# p7ii-001.net
KiCad netlist of a schematic drawn in EAGLE
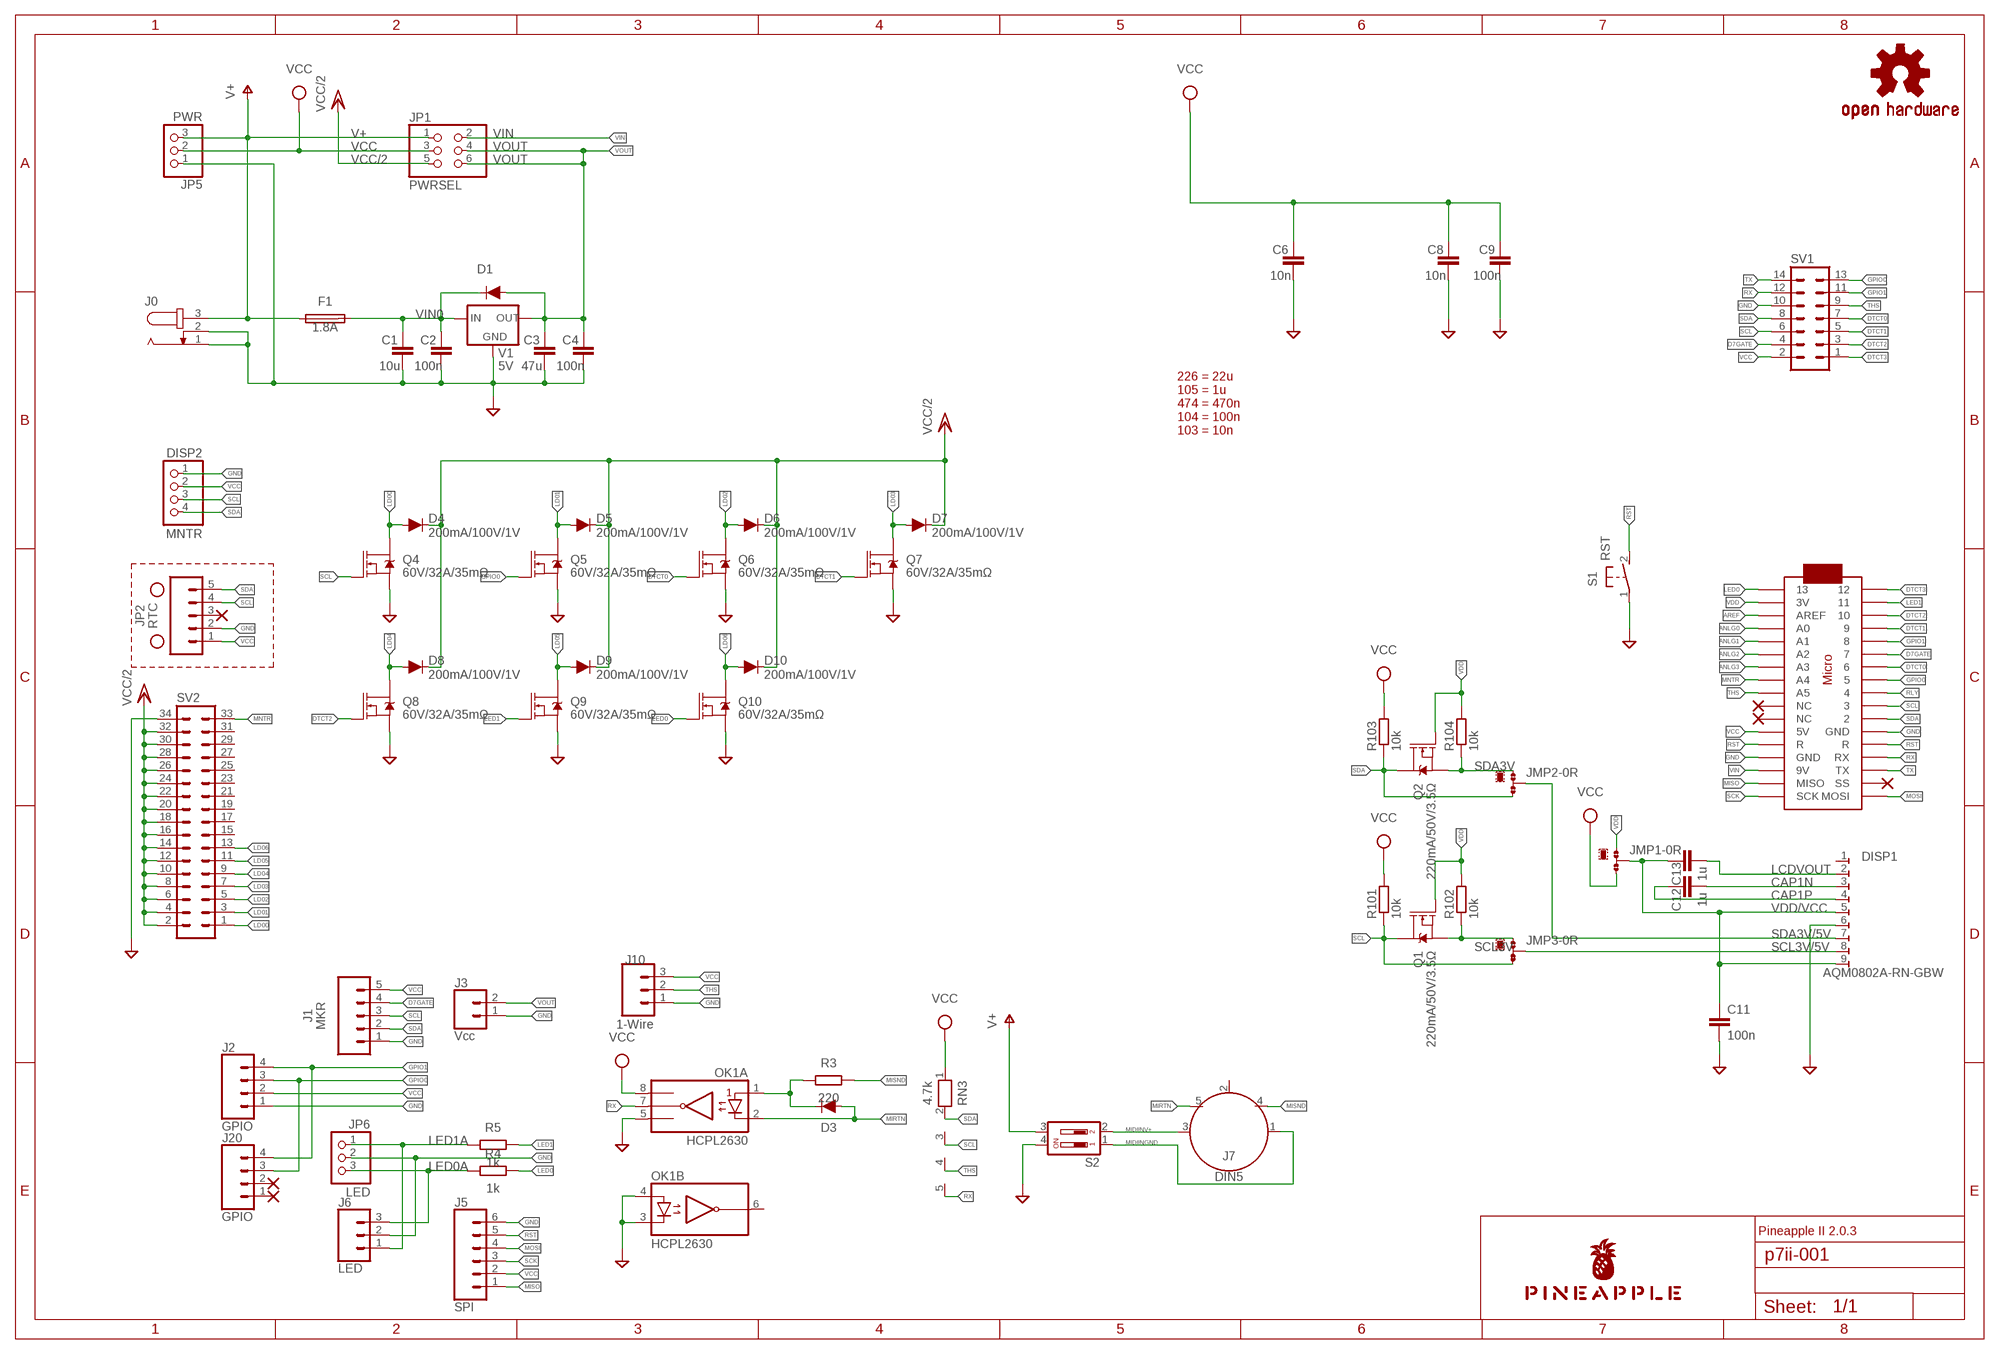
[diagram p0: schematic, sheet 1]

(export (version "E")
  (design (tool "Eeschema 10.0.6"))
  (components
    (comp (ref "C1")
      (value "10u")
      (footprint "eagle-import:C025-030X050")
      (libsource (lib "eagle-import") (part "C-EU025-030X050"))
    )
    (comp (ref "C2")
      (value "100n")
      (footprint "eagle-import:C025-024X044")
      (libsource (lib "eagle-import") (part "C-EU025-024X044"))
    )
    (comp (ref "C3")
      (value "47u")
      (footprint "eagle-import:C025-050X050")
      (libsource (lib "eagle-import") (part "C-EU025-050X050"))
    )
    (comp (ref "C4")
      (value "100n")
      (footprint "eagle-import:C025-024X044")
      (libsource (lib "eagle-import") (part "C-EU025-024X044"))
    )
    (comp (ref "C6")
      (value "10n")
      (footprint "eagle-import:C025-024X044")
      (libsource (lib "eagle-import") (part "resistor_348_C-EU025-024X044"))
    )
    (comp (ref "C8")
      (value "10n")
      (footprint "eagle-import:C025-024X044")
      (libsource (lib "eagle-import") (part "resistor_348_C-EU025-024X044"))
    )
    (comp (ref "C9")
      (value "100n")
      (footprint "eagle-import:C025-024X044")
      (libsource (lib "eagle-import") (part "resistor_348_C-EU025-024X044"))
    )
    (comp (ref "C11")
      (value "100n")
      (footprint "eagle-import:C025-024X044")
      (libsource (lib "eagle-import") (part "C-EU025-024X044"))
    )
    (comp (ref "C12")
      (value "1u")
      (footprint "eagle-import:C050-024X044")
      (libsource (lib "eagle-import") (part "C-EU050-024X044"))
    )
    (comp (ref "C13")
      (value "1u")
      (footprint "eagle-import:C050-024X044")
      (libsource (lib "eagle-import") (part "C-EU050-024X044"))
    )
    (comp (ref "D1")
      (value "DIODE-1N4148")
      (footprint "eagle-import:DIODE-1N4148")
      (libsource (lib "eagle-import") (part "DIODE-1N4148"))
    )
    (comp (ref "D3")
      (value "DIODE-1N4148")
      (footprint "eagle-import:DIODE-1N4148")
      (libsource (lib "eagle-import") (part "DIODE-1N4148"))
    )
    (comp (ref "D4")
      (value "200mA/100V/1V")
      (footprint "eagle-import:DIODE-1N4148")
      (libsource (lib "eagle-import") (part "DIODE-1N4148"))
    )
    (comp (ref "D5")
      (value "200mA/100V/1V")
      (footprint "eagle-import:DIODE-1N4148")
      (libsource (lib "eagle-import") (part "DIODE-1N4148"))
    )
    (comp (ref "D6")
      (value "200mA/100V/1V")
      (footprint "eagle-import:DIODE-1N4148")
      (libsource (lib "eagle-import") (part "DIODE-1N4148"))
    )
    (comp (ref "D7")
      (value "200mA/100V/1V")
      (footprint "eagle-import:DIODE-1N4148")
      (libsource (lib "eagle-import") (part "DIODE-1N4148"))
    )
    (comp (ref "D8")
      (value "200mA/100V/1V")
      (footprint "eagle-import:DIODE-1N4148")
      (libsource (lib "eagle-import") (part "DIODE-1N4148"))
    )
    (comp (ref "D9")
      (value "200mA/100V/1V")
      (footprint "eagle-import:DIODE-1N4148")
      (libsource (lib "eagle-import") (part "DIODE-1N4148"))
    )
    (comp (ref "D10")
      (value "200mA/100V/1V")
      (footprint "eagle-import:DIODE-1N4148")
      (libsource (lib "eagle-import") (part "DIODE-1N4148"))
    )
    (comp (ref "DISP1")
      (value "AQM0802A-RN-GBW")
      (footprint "eagle-import:AQM0802A-RN-GBW-FOOTPRINT")
      (libsource (lib "eagle-import") (part "AQM0802A-RN-GBW"))
    )
    (comp (ref "DISP2")
      (value "MNTR")
      (footprint "eagle-import:1X04")
      (libsource (lib "eagle-import") (part "PINHD-1X4"))
    )
    (comp (ref "F1")
      (value "1.8A")
      (footprint "eagle-import:TE5")
      (libsource (lib "eagle-import") (part "TE5"))
    )
    (comp (ref "H1")
      (value "STAND-OFF")
      (footprint "eagle-import:STAND-OFF")
      (libsource (lib "eagle-import") (part "STAND-OFF"))
    )
    (comp (ref "H2")
      (value "STAND-OFF")
      (footprint "eagle-import:STAND-OFF")
      (libsource (lib "eagle-import") (part "STAND-OFF"))
    )
    (comp (ref "J0")
      (value "JACK-PLUG0")
      (footprint "eagle-import:SPC4077")
      (libsource (lib "eagle-import") (part "JACK-PLUG0"))
    )
    (comp (ref "J1")
      (value "MKR")
      (footprint "eagle-import:JST-5-PTH")
      (libsource (lib "eagle-import") (part "CONN_05JST"))
    )
    (comp (ref "J2")
      (value "GPIO")
      (footprint "eagle-import:JST-4-PTH")
      (libsource (lib "eagle-import") (part "CONN_04JST-PTH"))
    )
    (comp (ref "J3")
      (value "Vcc")
      (footprint "eagle-import:JST-2-PTH")
      (libsource (lib "eagle-import") (part "CONN_02JST-PTH-2"))
    )
    (comp (ref "J5")
      (value "SPI")
      (footprint "eagle-import:1X06_1.27MM")
      (libsource (lib "eagle-import") (part "CONN_061.27MM"))
    )
    (comp (ref "J6")
      (value "LED")
      (footprint "eagle-import:JST-3-PTH-VERT")
      (libsource (lib "eagle-import") (part "CONN_03JST-PTH-VERT"))
    )
    (comp (ref "J7")
      (value "DIN5")
      (footprint "eagle-import:DIN5-RA-PTH")
      (libsource (lib "eagle-import") (part "DIN5"))
    )
    (comp (ref "J10")
      (value "1-Wire")
      (footprint "eagle-import:JST-3-PTH-VERT")
      (libsource (lib "eagle-import") (part "CONN_03JST-PTH-VERT"))
    )
    (comp (ref "J20")
      (value "GPIO")
      (footprint "eagle-import:1X04_1.27MM")
      (libsource (lib "eagle-import") (part "CONN_041.27MM"))
    )
    (comp (ref "JMP1")
      (value "0R-JUMPA")
      (footprint "eagle-import:A0R-JMP")
      (libsource (lib "eagle-import") (part "0R-JUMPA"))
    )
    (comp (ref "JMP2")
      (value "0R-JUMPA")
      (footprint "eagle-import:A0R-JMP")
      (libsource (lib "eagle-import") (part "0R-JUMPA"))
    )
    (comp (ref "JMP3")
      (value "0R-JUMPA")
      (footprint "eagle-import:A0R-JMP")
      (libsource (lib "eagle-import") (part "0R-JUMPA"))
    )
    (comp (ref "JP1")
      (value "PWRSEL")
      (footprint "eagle-import:2X03")
      (libsource (lib "eagle-import") (part "PINHD-2X3"))
    )
    (comp (ref "JP2")
      (value "RTC")
      (footprint "eagle-import:1X05")
      (libsource (lib "eagle-import") (part "CONN_05"))
    )
    (comp (ref "JP5")
      (value "PWR")
      (footprint "eagle-import:1X03")
      (libsource (lib "eagle-import") (part "PINHD-1X3"))
    )
    (comp (ref "JP6")
      (value "LED")
      (footprint "eagle-import:1X03")
      (libsource (lib "eagle-import") (part "PINHD-1X3"))
    )
    (comp (ref "LOGO1")
      (value "OSHW-LOGOS-COPPER")
      (footprint "eagle-import:OSHW-LOGO-S_COPPER")
      (libsource (lib "eagle-import") (part "OSHW-LOGOS-COPPER"))
    )
    (comp (ref "MC1")
      (value "ARDUINOMICRO")
      (footprint "eagle-import:ARDUINOMICRO")
      (libsource (lib "eagle-import") (part "ARDUINOMICRO"))
    )
    (comp (ref "OK1")
      (value "HCPL2630")
      (footprint "eagle-import:DIL08")
      (fields (field (name "MF") "AGILENT TECHNOLOGIES") (field (name "MPN") "HCPL-2630-000E"))
      (libsource (lib "eagle-import") (part "HCPL2630"))
    )
    (comp (ref "Q1")
      (value "220mA/50V/3.5Ω")
      (footprint "eagle-import:SOT23-3")
      (libsource (lib "eagle-import") (part "MOSFET-NCH-BSS138"))
    )
    (comp (ref "Q2")
      (value "220mA/50V/3.5Ω")
      (footprint "eagle-import:SOT23-3")
      (libsource (lib "eagle-import") (part "MOSFET-NCH-BSS138"))
    )
    (comp (ref "Q4")
      (value "60V/32A/35mΩ")
      (footprint "eagle-import:TO220V")
      (libsource (lib "eagle-import") (part "MOSFET-NCH-FQP30N06L"))
    )
    (comp (ref "Q5")
      (value "60V/32A/35mΩ")
      (footprint "eagle-import:TO220V")
      (libsource (lib "eagle-import") (part "MOSFET-NCH-FQP30N06L"))
    )
    (comp (ref "Q6")
      (value "60V/32A/35mΩ")
      (footprint "eagle-import:TO220V")
      (libsource (lib "eagle-import") (part "MOSFET-NCH-FQP30N06L"))
    )
    (comp (ref "Q7")
      (value "60V/32A/35mΩ")
      (footprint "eagle-import:TO220V")
      (libsource (lib "eagle-import") (part "MOSFET-NCH-FQP30N06L"))
    )
    (comp (ref "Q8")
      (value "60V/32A/35mΩ")
      (footprint "eagle-import:TO220V")
      (libsource (lib "eagle-import") (part "MOSFET-NCH-FQP30N06L"))
    )
    (comp (ref "Q9")
      (value "60V/32A/35mΩ")
      (footprint "eagle-import:TO220V")
      (libsource (lib "eagle-import") (part "MOSFET-NCH-FQP30N06L"))
    )
    (comp (ref "Q10")
      (value "60V/32A/35mΩ")
      (footprint "eagle-import:TO220V")
      (libsource (lib "eagle-import") (part "MOSFET-NCH-FQP30N06L"))
    )
    (comp (ref "R3")
      (value "220")
      (footprint "eagle-import:0204_5")
      (libsource (lib "eagle-import") (part "resistor_348_R-EU_0204/5"))
    )
    (comp (ref "R4")
      (value "1k")
      (footprint "eagle-import:0204_5")
      (libsource (lib "eagle-import") (part "resistor_348_R-EU_0204/5"))
    )
    (comp (ref "R5")
      (value "1k")
      (footprint "eagle-import:0204_5")
      (libsource (lib "eagle-import") (part "resistor_348_R-EU_0204/5"))
    )
    (comp (ref "R101")
      (value "10k")
      (footprint "eagle-import:M2012")
      (libsource (lib "eagle-import") (part "R-EU_M2012"))
    )
    (comp (ref "R102")
      (value "10k")
      (footprint "eagle-import:M2012")
      (libsource (lib "eagle-import") (part "R-EU_M2012"))
    )
    (comp (ref "R103")
      (value "10k")
      (footprint "eagle-import:M2012")
      (libsource (lib "eagle-import") (part "R-EU_M2012"))
    )
    (comp (ref "R104")
      (value "10k")
      (footprint "eagle-import:M2012")
      (libsource (lib "eagle-import") (part "R-EU_M2012"))
    )
    (comp (ref "RN3")
      (value "4.7k")
      (footprint "eagle-import:RN-5")
      (libsource (lib "eagle-import") (part "RN04"))
    )
    (comp (ref "S1")
      (value "RST")
      (footprint "eagle-import:B3F-31XX")
      (fields (field (name "MPN") "B3F-3100"))
      (libsource (lib "eagle-import") (part "31-XX"))
    )
    (comp (ref "S2")
      (value "DIP02YL")
      (footprint "eagle-import:DIP02YL")
      (libsource (lib "eagle-import") (part "DIP02YL"))
    )
    (comp (ref "SV1")
      (value "ML14")
      (footprint "eagle-import:ML14")
      (libsource (lib "eagle-import") (part "ML14"))
    )
    (comp (ref "SV2")
      (value "ML34L")
      (footprint "eagle-import:ML34L")
      (libsource (lib "eagle-import") (part "ML34L"))
    )
    (comp (ref "U$1")
      (value "PINEAPPLE450_SILK")
      (footprint "eagle-import:PINEAPPLE450_SILK")
      (libsource (lib "eagle-import") (part "PINEAPPLE450_SILK"))
    )
    (comp (ref "V1")
      (value "5V")
      (footprint "eagle-import:78XXS")
      (libsource (lib "eagle-import") (part "78XXS"))
    )
  )
  (nets
    (net (code "1") (name "/CAP1N") (class "Default")
      (node (ref "C12") (pin "2") (pinfunction "2_2") (pintype "passive"))
      (node (ref "DISP1") (pin "3") (pinfunction "3_3") (pintype "passive"))
    )
    (net (code "2") (name "/CAP1P") (class "Default")
      (node (ref "C12") (pin "1") (pinfunction "1_1") (pintype "passive"))
      (node (ref "DISP1") (pin "4") (pinfunction "4_4") (pintype "passive"))
    )
    (net (code "3") (name "/LCDVOUT") (class "Default")
      (node (ref "C13") (pin "2") (pinfunction "2_2") (pintype "passive"))
      (node (ref "DISP1") (pin "2") (pinfunction "2_2") (pintype "passive"))
    )
    (net (code "4") (name "/LED0A") (class "Default")
      (node (ref "J6") (pin "3") (pinfunction "3_3") (pintype "passive"))
      (node (ref "JP6") (pin "3") (pinfunction "3_3") (pintype "passive"))
      (node (ref "R4") (pin "1") (pinfunction "1_1") (pintype "passive"))
    )
    (net (code "5") (name "/LED1A") (class "Default")
      (node (ref "J6") (pin "1") (pinfunction "1_1") (pintype "passive"))
      (node (ref "JP6") (pin "1") (pinfunction "1_1") (pintype "passive"))
      (node (ref "R5") (pin "1") (pinfunction "1_1") (pintype "passive"))
    )
    (net (code "6") (name "/MIDIINGND") (class "Default")
      (node (ref "J7") (pin "1") (pinfunction "1_1") (pintype "bidirectional"))
      (node (ref "S2") (pin "1") (pinfunction "1_1") (pintype "passive"))
    )
    (net (code "7") (name "/MIDIINV+") (class "Default")
      (node (ref "J7") (pin "3") (pinfunction "3_3") (pintype "bidirectional"))
      (node (ref "S2") (pin "2") (pinfunction "2_2") (pintype "passive"))
    )
    (net (code "8") (name "/SCL3V") (class "Default")
      (node (ref "JMP3") (pin "1") (pinfunction "1_1") (pintype "passive"))
      (node (ref "Q1") (pin "2") (pinfunction "S_2") (pintype "bidirectional"))
      (node (ref "R102") (pin "1") (pinfunction "1_1") (pintype "passive"))
    )
    (net (code "9") (name "/SCL3V{slash}5V") (class "Default")
      (node (ref "DISP1") (pin "8") (pinfunction "8_8") (pintype "passive"))
      (node (ref "JMP3") (pin "2") (pinfunction "2_2") (pintype "passive"))
    )
    (net (code "10") (name "/SDA3V") (class "Default")
      (node (ref "JMP2") (pin "1") (pinfunction "1_1") (pintype "passive"))
      (node (ref "Q2") (pin "2") (pinfunction "S_2") (pintype "bidirectional"))
      (node (ref "R104") (pin "1") (pinfunction "1_1") (pintype "passive"))
    )
    (net (code "11") (name "/SDA3V{slash}5V") (class "Default")
      (node (ref "DISP1") (pin "7") (pinfunction "7_7") (pintype "passive"))
      (node (ref "JMP2") (pin "2") (pinfunction "2_2") (pintype "passive"))
    )
    (net (code "12") (name "/VDD{slash}VCC") (class "Default")
      (node (ref "C11") (pin "1") (pinfunction "1_1") (pintype "passive"))
      (node (ref "C13") (pin "1") (pinfunction "1_1") (pintype "passive"))
      (node (ref "DISP1") (pin "5") (pinfunction "5_5") (pintype "passive"))
      (node (ref "DISP1") (pin "9") (pinfunction "9_9") (pintype "passive"))
      (node (ref "JMP1") (pin "2") (pinfunction "2_2") (pintype "passive"))
    )
    (net (code "13") (name "/VIN0") (class "Default")
      (node (ref "C1") (pin "1") (pinfunction "1_1") (pintype "passive"))
      (node (ref "C2") (pin "1") (pinfunction "1_1") (pintype "passive"))
      (node (ref "D1") (pin "C") (pinfunction "C_C") (pintype "passive"))
      (node (ref "F1") (pin "2") (pinfunction "2_2") (pintype "passive"))
      (node (ref "V1") (pin "IN") (pinfunction "IN_IN") (pintype "input"))
    )
    (net (code "14") (name "ANLG0") (class "Default")
      (node (ref "MC1") (pin "P$31") (pinfunction "A0_P$31") (pintype "bidirectional"))
    )
    (net (code "15") (name "ANLG1") (class "Default")
      (node (ref "MC1") (pin "P$30") (pinfunction "A1_P$30") (pintype "bidirectional"))
    )
    (net (code "16") (name "ANLG2") (class "Default")
      (node (ref "MC1") (pin "P$29") (pinfunction "A2_P$29") (pintype "bidirectional"))
    )
    (net (code "17") (name "ANLG3") (class "Default")
      (node (ref "MC1") (pin "P$28") (pinfunction "A3_P$28") (pintype "bidirectional"))
    )
    (net (code "18") (name "AREF") (class "Default")
      (node (ref "MC1") (pin "P$32") (pinfunction "AREF_P$32") (pintype "bidirectional"))
    )
    (net (code "19") (name "D7GATE") (class "Default")
      (node (ref "J1") (pin "4") (pinfunction "4_4") (pintype "passive"))
      (node (ref "MC1") (pin "P$6") (pinfunction "7_P$6") (pintype "bidirectional"))
      (node (ref "SV1") (pin "4") (pinfunction "4_4") (pintype "passive"))
    )
    (net (code "20") (name "DTCT0") (class "Default")
      (node (ref "MC1") (pin "P$7") (pinfunction "6_P$7") (pintype "bidirectional"))
      (node (ref "Q6") (pin "1") (pinfunction "G_1") (pintype "bidirectional"))
      (node (ref "SV1") (pin "7") (pinfunction "7_7") (pintype "passive"))
    )
    (net (code "21") (name "DTCT1") (class "Default")
      (node (ref "MC1") (pin "P$4") (pinfunction "9_P$4") (pintype "bidirectional"))
      (node (ref "Q7") (pin "1") (pinfunction "G_1") (pintype "bidirectional"))
      (node (ref "SV1") (pin "5") (pinfunction "5_5") (pintype "passive"))
    )
    (net (code "22") (name "DTCT2") (class "Default")
      (node (ref "MC1") (pin "P$3") (pinfunction "10_P$3") (pintype "bidirectional"))
      (node (ref "Q8") (pin "1") (pinfunction "G_1") (pintype "bidirectional"))
      (node (ref "SV1") (pin "3") (pinfunction "3_3") (pintype "passive"))
    )
    (net (code "23") (name "DTCT3") (class "Default")
      (node (ref "MC1") (pin "P$1") (pinfunction "12_P$1") (pintype "bidirectional"))
      (node (ref "SV1") (pin "1") (pinfunction "1_1") (pintype "passive"))
    )
    (net (code "24") (name "GND") (class "Default")
      (node (ref "C1") (pin "2") (pinfunction "2_2") (pintype "passive"))
      (node (ref "C11") (pin "2") (pinfunction "2_2") (pintype "passive"))
      (node (ref "C2") (pin "2") (pinfunction "2_2") (pintype "passive"))
      (node (ref "C3") (pin "2") (pinfunction "2_2") (pintype "passive"))
      (node (ref "C4") (pin "2") (pinfunction "2_2") (pintype "passive"))
      (node (ref "C6") (pin "2") (pinfunction "2_2") (pintype "passive"))
      (node (ref "C8") (pin "2") (pinfunction "2_2") (pintype "passive"))
      (node (ref "C9") (pin "2") (pinfunction "2_2") (pintype "passive"))
      (node (ref "DISP1") (pin "6") (pinfunction "6_6") (pintype "passive"))
      (node (ref "DISP2") (pin "1") (pinfunction "1_1") (pintype "passive"))
      (node (ref "J0") (pin "1") (pinfunction "1_1") (pintype "passive"))
      (node (ref "J0") (pin "2") (pinfunction "2_2") (pintype "passive"))
      (node (ref "J1") (pin "1") (pinfunction "1_1") (pintype "passive"))
      (node (ref "J10") (pin "1") (pinfunction "1_1") (pintype "passive"))
      (node (ref "J2") (pin "1") (pinfunction "1_1") (pintype "passive"))
      (node (ref "J3") (pin "1") (pinfunction "1_1") (pintype "passive"))
      (node (ref "J5") (pin "6") (pinfunction "6_6") (pintype "passive"))
      (node (ref "J6") (pin "2") (pinfunction "2_2") (pintype "passive"))
      (node (ref "JP2") (pin "2") (pinfunction "2_2") (pintype "passive"))
      (node (ref "JP5") (pin "1") (pinfunction "1_1") (pintype "passive"))
      (node (ref "JP6") (pin "2") (pinfunction "2_2") (pintype "passive"))
      (node (ref "MC1") (pin "P$12") (pinfunction "GND_P$12") (pintype "bidirectional"))
      (node (ref "MC1") (pin "P$21") (pinfunction "GND_P$21") (pintype "bidirectional"))
      (node (ref "OK1") (pin "3") (pinfunction "C2_3") (pintype "passive"))
      (node (ref "OK1") (pin "4") (pinfunction "A2_4") (pintype "passive"))
      (node (ref "OK1") (pin "5") (pinfunction "GND_5") (pintype "passive"))
      (node (ref "Q10") (pin "3") (pinfunction "S_3") (pintype "bidirectional"))
      (node (ref "Q4") (pin "3") (pinfunction "S_3") (pintype "bidirectional"))
      (node (ref "Q5") (pin "3") (pinfunction "S_3") (pintype "bidirectional"))
      (node (ref "Q6") (pin "3") (pinfunction "S_3") (pintype "bidirectional"))
      (node (ref "Q7") (pin "3") (pinfunction "S_3") (pintype "bidirectional"))
      (node (ref "Q8") (pin "3") (pinfunction "S_3") (pintype "bidirectional"))
      (node (ref "Q9") (pin "3") (pinfunction "S_3") (pintype "bidirectional"))
      (node (ref "S1") (pin "1") (pinfunction "P_1") (pintype "passive"))
      (node (ref "S2") (pin "4") (pinfunction "4_4") (pintype "passive"))
      (node (ref "SV1") (pin "10") (pinfunction "10_10") (pintype "passive"))
      (node (ref "SV2") (pin "34") (pinfunction "34_34") (pintype "passive"))
      (node (ref "V1") (pin "GND") (pinfunction "GND_GND") (pintype "input"))
    )
    (net (code "25") (name "GPIO0") (class "Default")
      (node (ref "J2") (pin "3") (pinfunction "3_3") (pintype "passive"))
      (node (ref "J20") (pin "3") (pinfunction "3_3") (pintype "passive"))
      (node (ref "MC1") (pin "P$8") (pinfunction "5_P$8") (pintype "bidirectional"))
      (node (ref "Q5") (pin "1") (pinfunction "G_1") (pintype "bidirectional"))
      (node (ref "SV1") (pin "13") (pinfunction "13_13") (pintype "passive"))
    )
    (net (code "26") (name "GPIO1") (class "Default")
      (node (ref "J2") (pin "4") (pinfunction "4_4") (pintype "passive"))
      (node (ref "J20") (pin "4") (pinfunction "4_4") (pintype "passive"))
      (node (ref "MC1") (pin "P$5") (pinfunction "8_P$5") (pintype "bidirectional"))
      (node (ref "SV1") (pin "11") (pinfunction "11_11") (pintype "passive"))
    )
    (net (code "27") (name "LD00") (class "Default")
      (node (ref "D4") (pin "A") (pinfunction "A_A") (pintype "passive"))
      (node (ref "Q4") (pin "2") (pinfunction "D_2") (pintype "bidirectional"))
      (node (ref "SV2") (pin "1") (pinfunction "1_1") (pintype "passive"))
    )
    (net (code "28") (name "LD01") (class "Default")
      (node (ref "D5") (pin "A") (pinfunction "A_A") (pintype "passive"))
      (node (ref "Q5") (pin "2") (pinfunction "D_2") (pintype "bidirectional"))
      (node (ref "SV2") (pin "3") (pinfunction "3_3") (pintype "passive"))
    )
    (net (code "29") (name "LD02") (class "Default")
      (node (ref "D6") (pin "A") (pinfunction "A_A") (pintype "passive"))
      (node (ref "Q6") (pin "2") (pinfunction "D_2") (pintype "bidirectional"))
      (node (ref "SV2") (pin "5") (pinfunction "5_5") (pintype "passive"))
    )
    (net (code "30") (name "LD03") (class "Default")
      (node (ref "D7") (pin "A") (pinfunction "A_A") (pintype "passive"))
      (node (ref "Q7") (pin "2") (pinfunction "D_2") (pintype "bidirectional"))
      (node (ref "SV2") (pin "7") (pinfunction "7_7") (pintype "passive"))
    )
    (net (code "31") (name "LD04") (class "Default")
      (node (ref "D8") (pin "A") (pinfunction "A_A") (pintype "passive"))
      (node (ref "Q8") (pin "2") (pinfunction "D_2") (pintype "bidirectional"))
      (node (ref "SV2") (pin "9") (pinfunction "9_9") (pintype "passive"))
    )
    (net (code "32") (name "LD05") (class "Default")
      (node (ref "D9") (pin "A") (pinfunction "A_A") (pintype "passive"))
      (node (ref "Q9") (pin "2") (pinfunction "D_2") (pintype "bidirectional"))
      (node (ref "SV2") (pin "11") (pinfunction "11_11") (pintype "passive"))
    )
    (net (code "33") (name "LD06") (class "Default")
      (node (ref "D10") (pin "A") (pinfunction "A_A") (pintype "passive"))
      (node (ref "Q10") (pin "2") (pinfunction "D_2") (pintype "bidirectional"))
      (node (ref "SV2") (pin "13") (pinfunction "13_13") (pintype "passive"))
    )
    (net (code "34") (name "LED0") (class "Default")
      (node (ref "MC1") (pin "P$34") (pinfunction "13_P$34") (pintype "bidirectional"))
      (node (ref "Q10") (pin "1") (pinfunction "G_1") (pintype "bidirectional"))
      (node (ref "R4") (pin "2") (pinfunction "2_2") (pintype "passive"))
    )
    (net (code "35") (name "LED1") (class "Default")
      (node (ref "MC1") (pin "P$2") (pinfunction "11_P$2") (pintype "bidirectional"))
      (node (ref "Q9") (pin "1") (pinfunction "G_1") (pintype "bidirectional"))
      (node (ref "R5") (pin "2") (pinfunction "2_2") (pintype "passive"))
    )
    (net (code "36") (name "MIRTN") (class "Default")
      (node (ref "D3") (pin "A") (pinfunction "A_A") (pintype "passive"))
      (node (ref "J7") (pin "5") (pinfunction "5_5") (pintype "bidirectional"))
      (node (ref "OK1") (pin "2") (pinfunction "C1_2") (pintype "passive"))
    )
    (net (code "37") (name "MISND") (class "Default")
      (node (ref "J7") (pin "4") (pinfunction "4_4") (pintype "bidirectional"))
      (node (ref "R3") (pin "2") (pinfunction "2_2") (pintype "passive"))
    )
    (net (code "38") (name "MISO") (class "Default")
      (node (ref "J5") (pin "1") (pinfunction "1_1") (pintype "passive"))
      (node (ref "MC1") (pin "P$19") (pinfunction "MISO_P$19") (pintype "bidirectional"))
    )
    (net (code "39") (name "MNTR") (class "Default")
      (node (ref "MC1") (pin "P$27") (pinfunction "A4_P$27") (pintype "bidirectional"))
      (node (ref "SV2") (pin "33") (pinfunction "33_33") (pintype "passive"))
    )
    (net (code "40") (name "MOSI") (class "Default")
      (node (ref "J5") (pin "4") (pinfunction "4_4") (pintype "passive"))
      (node (ref "MC1") (pin "P$17") (pinfunction "MOSI_P$17") (pintype "bidirectional"))
    )
    (net (code "41") (name "Net-(OK1A-A1)") (class "Default")
      (node (ref "D3") (pin "C") (pinfunction "C_C") (pintype "passive"))
      (node (ref "OK1") (pin "1") (pinfunction "A1_1") (pintype "passive"))
      (node (ref "R3") (pin "1") (pinfunction "1_1") (pintype "passive"))
    )
    (net (code "42") (name "RLY") (class "Default")
      (node (ref "MC1") (pin "P$9") (pinfunction "4_P$9") (pintype "bidirectional"))
    )
    (net (code "43") (name "RST") (class "Default")
      (node (ref "J5") (pin "5") (pinfunction "5_5") (pintype "passive"))
      (node (ref "MC1") (pin "P$13") (pinfunction "R_P$13") (pintype "bidirectional"))
      (node (ref "MC1") (pin "P$22") (pinfunction "R_P$22") (pintype "bidirectional"))
      (node (ref "S1") (pin "2") (pinfunction "S_2") (pintype "passive"))
    )
    (net (code "44") (name "RX") (class "Default")
      (node (ref "MC1") (pin "P$14") (pinfunction "RX_P$14") (pintype "bidirectional"))
      (node (ref "OK1") (pin "7") (pinfunction "VO1_7") (pintype "passive"))
      (node (ref "RN3") (pin "5") (pinfunction "5_5") (pintype "passive"))
      (node (ref "SV1") (pin "12") (pinfunction "12_12") (pintype "passive"))
    )
    (net (code "45") (name "SCK") (class "Default")
      (node (ref "J5") (pin "3") (pinfunction "3_3") (pintype "passive"))
      (node (ref "MC1") (pin "P$18") (pinfunction "SCK_P$18") (pintype "bidirectional"))
    )
    (net (code "46") (name "SCL") (class "Default")
      (node (ref "DISP2") (pin "3") (pinfunction "3_3") (pintype "passive"))
      (node (ref "J1") (pin "3") (pinfunction "3_3") (pintype "passive"))
      (node (ref "JMP3") (pin "3") (pinfunction "3_3") (pintype "passive"))
      (node (ref "JP2") (pin "4") (pinfunction "4_4") (pintype "passive"))
      (node (ref "MC1") (pin "P$10") (pinfunction "3_P$10") (pintype "bidirectional"))
      (node (ref "Q1") (pin "3") (pinfunction "D_3") (pintype "bidirectional"))
      (node (ref "Q4") (pin "1") (pinfunction "G_1") (pintype "bidirectional"))
      (node (ref "R101") (pin "1") (pinfunction "1_1") (pintype "passive"))
      (node (ref "RN3") (pin "3") (pinfunction "3_3") (pintype "passive"))
      (node (ref "SV1") (pin "6") (pinfunction "6_6") (pintype "passive"))
    )
    (net (code "47") (name "SDA") (class "Default")
      (node (ref "DISP2") (pin "4") (pinfunction "4_4") (pintype "passive"))
      (node (ref "J1") (pin "2") (pinfunction "2_2") (pintype "passive"))
      (node (ref "JMP2") (pin "3") (pinfunction "3_3") (pintype "passive"))
      (node (ref "JP2") (pin "5") (pinfunction "5_5") (pintype "passive"))
      (node (ref "MC1") (pin "P$11") (pinfunction "2_P$11") (pintype "bidirectional"))
      (node (ref "Q2") (pin "3") (pinfunction "D_3") (pintype "bidirectional"))
      (node (ref "R103") (pin "1") (pinfunction "1_1") (pintype "passive"))
      (node (ref "RN3") (pin "2") (pinfunction "2_2") (pintype "passive"))
      (node (ref "SV1") (pin "8") (pinfunction "8_8") (pintype "passive"))
    )
    (net (code "48") (name "THS") (class "Default")
      (node (ref "J10") (pin "2") (pinfunction "2_2") (pintype "passive"))
      (node (ref "MC1") (pin "P$26") (pinfunction "A5_P$26") (pintype "bidirectional"))
      (node (ref "RN3") (pin "4") (pinfunction "4_4") (pintype "passive"))
      (node (ref "SV1") (pin "9") (pinfunction "9_9") (pintype "passive"))
    )
    (net (code "49") (name "TX") (class "Default")
      (node (ref "MC1") (pin "P$15") (pinfunction "TX_P$15") (pintype "bidirectional"))
      (node (ref "SV1") (pin "14") (pinfunction "14_14") (pintype "passive"))
    )
    (net (code "50") (name "V+") (class "Default")
      (node (ref "F1") (pin "1") (pinfunction "1_1") (pintype "passive"))
      (node (ref "J0") (pin "3") (pinfunction "3_3") (pintype "passive"))
      (node (ref "JP1") (pin "1") (pinfunction "1_1") (pintype "passive"))
      (node (ref "JP5") (pin "3") (pinfunction "3_3") (pintype "passive"))
      (node (ref "S2") (pin "3") (pinfunction "3_3") (pintype "passive"))
    )
    (net (code "51") (name "VCC") (class "Default")
      (node (ref "C6") (pin "1") (pinfunction "1_1") (pintype "passive"))
      (node (ref "C8") (pin "1") (pinfunction "1_1") (pintype "passive"))
      (node (ref "C9") (pin "1") (pinfunction "1_1") (pintype "passive"))
      (node (ref "DISP2") (pin "2") (pinfunction "2_2") (pintype "passive"))
      (node (ref "J1") (pin "5") (pinfunction "5_5") (pintype "passive"))
      (node (ref "J10") (pin "3") (pinfunction "3_3") (pintype "passive"))
      (node (ref "J2") (pin "2") (pinfunction "2_2") (pintype "passive"))
      (node (ref "J5") (pin "2") (pinfunction "2_2") (pintype "passive"))
      (node (ref "JMP1") (pin "3") (pinfunction "3_3") (pintype "passive"))
      (node (ref "JP1") (pin "3") (pinfunction "3_3") (pintype "passive"))
      (node (ref "JP2") (pin "1") (pinfunction "1_1") (pintype "passive"))
      (node (ref "JP5") (pin "2") (pinfunction "2_2") (pintype "passive"))
      (node (ref "MC1") (pin "P$23") (pinfunction "5V_P$23") (pintype "bidirectional"))
      (node (ref "OK1") (pin "8") (pinfunction "VCC_8") (pintype "passive"))
      (node (ref "R101") (pin "2") (pinfunction "2_2") (pintype "passive"))
      (node (ref "R103") (pin "2") (pinfunction "2_2") (pintype "passive"))
      (node (ref "RN3") (pin "1") (pinfunction "1_1") (pintype "passive"))
      (node (ref "SV1") (pin "2") (pinfunction "2_2") (pintype "passive"))
    )
    (net (code "52") (name "VCC{slash}2") (class "Default")
      (node (ref "D10") (pin "C") (pinfunction "C_C") (pintype "passive"))
      (node (ref "D4") (pin "C") (pinfunction "C_C") (pintype "passive"))
      (node (ref "D5") (pin "C") (pinfunction "C_C") (pintype "passive"))
      (node (ref "D6") (pin "C") (pinfunction "C_C") (pintype "passive"))
      (node (ref "D7") (pin "C") (pinfunction "C_C") (pintype "passive"))
      (node (ref "D8") (pin "C") (pinfunction "C_C") (pintype "passive"))
      (node (ref "D9") (pin "C") (pinfunction "C_C") (pintype "passive"))
      (node (ref "JP1") (pin "5") (pinfunction "5_5") (pintype "passive"))
      (node (ref "SV2") (pin "10") (pinfunction "10_10") (pintype "passive"))
      (node (ref "SV2") (pin "12") (pinfunction "12_12") (pintype "passive"))
      (node (ref "SV2") (pin "14") (pinfunction "14_14") (pintype "passive"))
      (node (ref "SV2") (pin "16") (pinfunction "16_16") (pintype "passive"))
      (node (ref "SV2") (pin "18") (pinfunction "18_18") (pintype "passive"))
      (node (ref "SV2") (pin "2") (pinfunction "2_2") (pintype "passive"))
      (node (ref "SV2") (pin "20") (pinfunction "20_20") (pintype "passive"))
      (node (ref "SV2") (pin "22") (pinfunction "22_22") (pintype "passive"))
      (node (ref "SV2") (pin "24") (pinfunction "24_24") (pintype "passive"))
      (node (ref "SV2") (pin "26") (pinfunction "26_26") (pintype "passive"))
      (node (ref "SV2") (pin "28") (pinfunction "28_28") (pintype "passive"))
      (node (ref "SV2") (pin "30") (pinfunction "30_30") (pintype "passive"))
      (node (ref "SV2") (pin "32") (pinfunction "32_32") (pintype "passive"))
      (node (ref "SV2") (pin "4") (pinfunction "4_4") (pintype "passive"))
      (node (ref "SV2") (pin "6") (pinfunction "6_6") (pintype "passive"))
      (node (ref "SV2") (pin "8") (pinfunction "8_8") (pintype "passive"))
    )
    (net (code "53") (name "VDD") (class "Default")
      (node (ref "JMP1") (pin "1") (pinfunction "1_1") (pintype "passive"))
      (node (ref "MC1") (pin "P$33") (pinfunction "3V_P$33") (pintype "bidirectional"))
      (node (ref "Q1") (pin "1") (pinfunction "G_1") (pintype "bidirectional"))
      (node (ref "Q2") (pin "1") (pinfunction "G_1") (pintype "bidirectional"))
      (node (ref "R102") (pin "2") (pinfunction "2_2") (pintype "passive"))
      (node (ref "R104") (pin "2") (pinfunction "2_2") (pintype "passive"))
    )
    (net (code "54") (name "VIN") (class "Default")
      (node (ref "JP1") (pin "2") (pinfunction "2_2") (pintype "passive"))
      (node (ref "MC1") (pin "P$20") (pinfunction "9V_P$20") (pintype "bidirectional"))
    )
    (net (code "55") (name "VOUT") (class "Default")
      (node (ref "C3") (pin "1") (pinfunction "1_1") (pintype "passive"))
      (node (ref "C4") (pin "1") (pinfunction "1_1") (pintype "passive"))
      (node (ref "D1") (pin "A") (pinfunction "A_A") (pintype "passive"))
      (node (ref "J3") (pin "2") (pinfunction "2_2") (pintype "passive"))
      (node (ref "JP1") (pin "4") (pinfunction "4_4") (pintype "passive"))
      (node (ref "JP1") (pin "6") (pinfunction "6_6") (pintype "passive"))
      (node (ref "V1") (pin "OUT") (pinfunction "OUT_OUT") (pintype "passive"))
    )
    (net (code "56") (name "unconnected-(DISP1-Pad1)") (class "Default")
      (node (ref "DISP1") (pin "1") (pinfunction "1_1") (pintype "passive"))
    )
    (net (code "57") (name "unconnected-(J7-Pad2)") (class "Default")
      (node (ref "J7") (pin "2") (pinfunction "2_2") (pintype "bidirectional"))
    )
    (net (code "58") (name "unconnected-(J20-Pad1)") (class "Default")
      (node (ref "J20") (pin "1") (pinfunction "1_1") (pintype "passive"))
    )
    (net (code "59") (name "unconnected-(J20-Pad2)") (class "Default")
      (node (ref "J20") (pin "2") (pinfunction "2_2") (pintype "passive"))
    )
    (net (code "60") (name "unconnected-(JP2-Pad3)") (class "Default")
      (node (ref "JP2") (pin "3") (pinfunction "3_3") (pintype "passive"))
    )
    (net (code "61") (name "unconnected-(MC1-NC-PadP$24)") (class "Default")
      (node (ref "MC1") (pin "P$24") (pinfunction "NC_P$24") (pintype "bidirectional"))
    )
    (net (code "62") (name "unconnected-(MC1-NC-PadP$25)") (class "Default")
      (node (ref "MC1") (pin "P$25") (pinfunction "NC_P$25") (pintype "bidirectional"))
    )
    (net (code "63") (name "unconnected-(MC1-SS-PadP$16)") (class "Default")
      (node (ref "MC1") (pin "P$16") (pinfunction "SS_P$16") (pintype "bidirectional"))
    )
    (net (code "64") (name "unconnected-(OK1B-VO2-Pad6)") (class "Default")
      (node (ref "OK1") (pin "6") (pinfunction "VO2_6") (pintype "passive"))
    )
    (net (code "65") (name "unconnected-(SV2-Pad15)") (class "Default")
      (node (ref "SV2") (pin "15") (pinfunction "15_15") (pintype "passive"))
    )
    (net (code "66") (name "unconnected-(SV2-Pad17)") (class "Default")
      (node (ref "SV2") (pin "17") (pinfunction "17_17") (pintype "passive"))
    )
    (net (code "67") (name "unconnected-(SV2-Pad19)") (class "Default")
      (node (ref "SV2") (pin "19") (pinfunction "19_19") (pintype "passive"))
    )
    (net (code "68") (name "unconnected-(SV2-Pad21)") (class "Default")
      (node (ref "SV2") (pin "21") (pinfunction "21_21") (pintype "passive"))
    )
    (net (code "69") (name "unconnected-(SV2-Pad23)") (class "Default")
      (node (ref "SV2") (pin "23") (pinfunction "23_23") (pintype "passive"))
    )
    (net (code "70") (name "unconnected-(SV2-Pad25)") (class "Default")
      (node (ref "SV2") (pin "25") (pinfunction "25_25") (pintype "passive"))
    )
    (net (code "71") (name "unconnected-(SV2-Pad27)") (class "Default")
      (node (ref "SV2") (pin "27") (pinfunction "27_27") (pintype "passive"))
    )
    (net (code "72") (name "unconnected-(SV2-Pad29)") (class "Default")
      (node (ref "SV2") (pin "29") (pinfunction "29_29") (pintype "passive"))
    )
    (net (code "73") (name "unconnected-(SV2-Pad31)") (class "Default")
      (node (ref "SV2") (pin "31") (pinfunction "31_31") (pintype "passive"))
    )
  )
)
